# 1302_07.net
KiCad netlist of a schematic drawn in Altium Designer
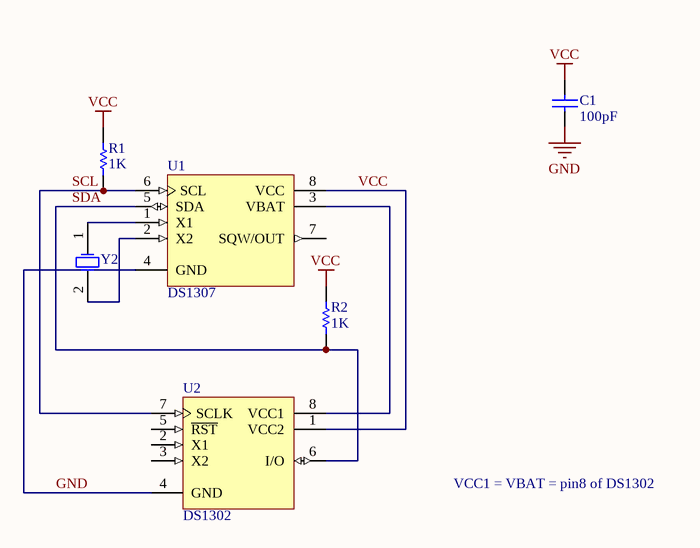
[diagram p0: 1302_07.SchDoc]

(export (version "E")
  (design (tool "Eeschema 10.0.6"))
  (components
    (comp (ref "C1")
      (value "100pF")
      (footprint "C1206")
      (description "Capacitor")
      (fields (field (name "Comment") ".1uF 1206") (field (name "PUBLISHER") "Altium Limited"))
      (libsource (lib "Miscellaneous Devices") (part "Cap"))
    )
    (comp (ref "R1")
      (value "1K")
      (footprint "R1206")
      (description "Resistor")
      (fields (field (name "Comment") "1K 1206") (field (name "PUBLISHER") "Altium Limited"))
      (libsource (lib "Miscellaneous Devices") (part "Res1"))
    )
    (comp (ref "R2")
      (value "1K")
      (footprint "R1206")
      (description "Resistor")
      (fields (field (name "Comment") "1K 1206") (field (name "PUBLISHER") "Altium Limited"))
      (libsource (lib "Miscellaneous Devices") (part "Res1"))
    )
    (comp (ref "U1")
      (value "DS1307")
      (footprint "DIP8")
      (description "64 X 8 Serial Real-Time Clock")
      (fields (field (name "PUBLISHER") "Altium Limited"))
      (libsource (lib "Dallas Peripheral Real Time Clock") (part "DS1307"))
    )
    (comp (ref "U2")
      (value "DS1302")
      (footprint "DIP8")
      (description "Trickle Charge Timekeeping Chip")
      (fields (field (name "PUBLISHER") "Altium Limited"))
      (libsource (lib "Dallas Peripheral Real Time Clock") (part "DS1302"))
    )
    (comp (ref "Y2")
      (value "XTAL 32.768KHz 6pF")
      (footprint "R38")
      (description "Crystal Oscillator")
      (fields (field (name "PUBLISHER") "Altium Limited"))
      (libsource (lib "Miscellaneous Devices") (part "XTAL"))
    )
  )
  (nets
    (net (code "1") (name "/SCL") (class "Default")
      (node (ref "R1") (pin "1") (pinfunction "1_1") (pintype "passive"))
      (node (ref "U1") (pin "6") (pinfunction "SCL_6") (pintype "input"))
      (node (ref "U2") (pin "7") (pinfunction "SCLK_7") (pintype "input"))
    )
    (net (code "2") (name "/SDA") (class "Default")
      (node (ref "R2") (pin "1") (pinfunction "1_1") (pintype "passive"))
      (node (ref "U1") (pin "5") (pinfunction "SDA_5") (pintype "bidirectional"))
      (node (ref "U2") (pin "6") (pinfunction "I/O_6") (pintype "bidirectional"))
    )
    (net (code "3") (name "GND") (class "Default")
      (node (ref "C1") (pin "1") (pinfunction "1_1") (pintype "passive"))
      (node (ref "U1") (pin "4") (pinfunction "GND_4") (pintype "power_in"))
      (node (ref "U2") (pin "4") (pinfunction "GND_4") (pintype "power_in"))
    )
    (net (code "4") (name "Net-(U1-VBAT)") (class "Default")
      (node (ref "U1") (pin "3") (pinfunction "VBAT_3") (pintype "power_in"))
      (node (ref "U2") (pin "8") (pinfunction "VCC1_8") (pintype "power_in"))
    )
    (net (code "5") (name "Net-(U1-X1)") (class "Default")
      (node (ref "U1") (pin "1") (pinfunction "X1_1") (pintype "input"))
      (node (ref "Y2") (pin "1") (pinfunction "OSC1_1") (pintype "passive"))
    )
    (net (code "6") (name "Net-(U1-X2)") (class "Default")
      (node (ref "U1") (pin "2") (pinfunction "X2_2") (pintype "input"))
      (node (ref "Y2") (pin "2") (pinfunction "OSC2_2") (pintype "passive"))
    )
    (net (code "7") (name "VCC") (class "Default")
      (node (ref "C1") (pin "2") (pinfunction "2_2") (pintype "passive"))
      (node (ref "R1") (pin "2") (pinfunction "2_2") (pintype "passive"))
      (node (ref "R2") (pin "2") (pinfunction "2_2") (pintype "passive"))
      (node (ref "U1") (pin "8") (pinfunction "VCC_8") (pintype "power_in"))
      (node (ref "U2") (pin "1") (pinfunction "VCC2_1") (pintype "power_in"))
    )
    (net (code "8") (name "unconnected-(U1-SQW{slash}OUT-Pad7)") (class "Default")
      (node (ref "U1") (pin "7") (pinfunction "SQW/OUT_7") (pintype "output"))
    )
    (net (code "9") (name "unconnected-(U2-X1-Pad2)") (class "Default")
      (node (ref "U2") (pin "2") (pinfunction "X1_2") (pintype "input"))
    )
    (net (code "10") (name "unconnected-(U2-X2-Pad3)") (class "Default")
      (node (ref "U2") (pin "3") (pinfunction "X2_3") (pintype "input"))
    )
    (net (code "11") (name "unconnected-(U2-~{RST}-Pad5)") (class "Default")
      (node (ref "U2") (pin "5") (pinfunction "~{RST}_5") (pintype "input"))
    )
  )
)
